# Sheet1.net
KiCad netlist of a schematic drawn in Altium Designer
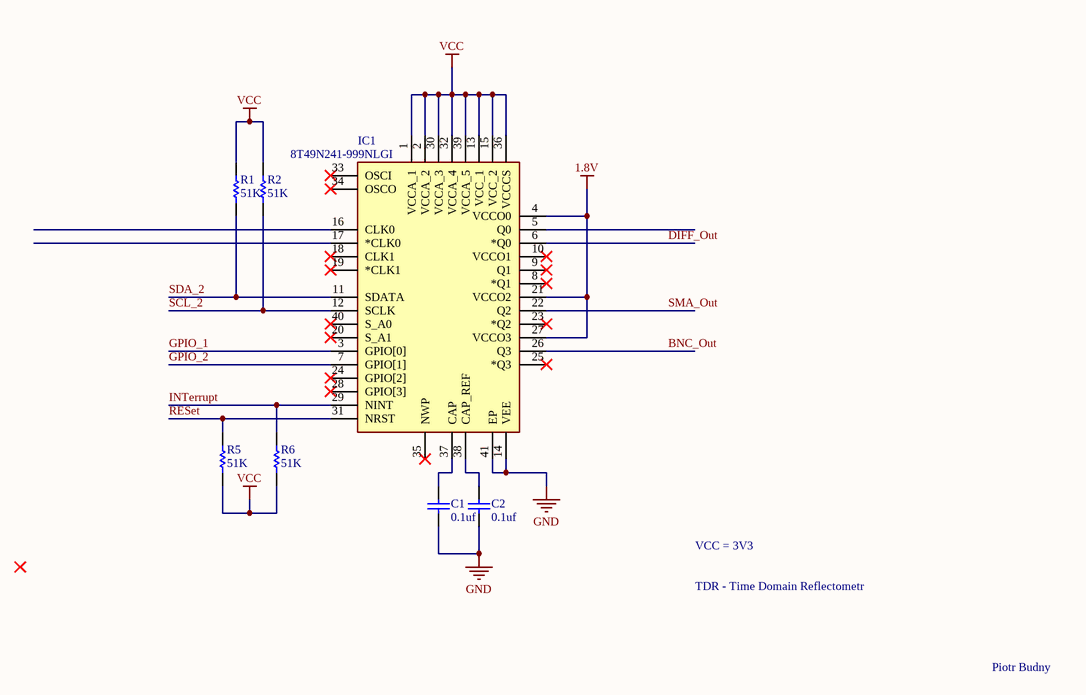
[diagram p0: Sheet1.SchDoc]

(export (version "E")
  (design (tool "Eeschema 10.0.6"))
  (components
    (comp (ref "C1")
      (value "0.1uf")
      (description "Capacitor")
      (libsource (lib "Simulation Generic Components") (part "Capacitor"))
    )
    (comp (ref "C2")
      (value "0.1uf")
      (description "Capacitor")
      (libsource (lib "Simulation Generic Components") (part "Capacitor"))
    )
    (comp (ref "IC1")
      (value "8T49N241-999NLGI")
      (footprint "SamacSys:QFN50P600X600X100-41N")
      (description "Integrated Circuit")
      (fields (field (name "MOUSER PART NUMBER") "972-8T49N241-999NLGI"))
      (libsource (lib "*") (part "8T49N241-999NLGI"))
    )
    (comp (ref "R1")
      (value "51K")
      (description "Resistor")
      (libsource (lib "Simulation Generic Components") (part "Resistor"))
    )
    (comp (ref "R2")
      (value "51K")
      (description "Resistor")
      (libsource (lib "Simulation Generic Components") (part "Resistor"))
    )
    (comp (ref "R5")
      (value "51K")
      (description "Resistor")
      (libsource (lib "Simulation Generic Components") (part "Resistor"))
    )
    (comp (ref "R6")
      (value "51K")
      (description "Resistor")
      (libsource (lib "Simulation Generic Components") (part "Resistor"))
    )
  )
  (nets
    (net (code "1") (name "/BNC_Out") (class "Default")
      (node (ref "IC1") (pin "26") (pinfunction "Q3_26") (pintype "passive"))
    )
    (net (code "2") (name "/DIFF_Out") (class "Default")
      (node (ref "IC1") (pin "6") (pinfunction "*Q0_6") (pintype "passive"))
    )
    (net (code "3") (name "/GPIO_1") (class "Default")
      (node (ref "IC1") (pin "3") (pinfunction "GPIO[0]_3") (pintype "passive"))
    )
    (net (code "4") (name "/GPIO_2") (class "Default")
      (node (ref "IC1") (pin "7") (pinfunction "GPIO[1]_7") (pintype "passive"))
    )
    (net (code "5") (name "/INTerrupt") (class "Default")
      (node (ref "IC1") (pin "29") (pinfunction "NINT_29") (pintype "passive"))
      (node (ref "R6") (pin "2") (pinfunction "2_2") (pintype "passive"))
    )
    (net (code "6") (name "/RESet") (class "Default")
      (node (ref "IC1") (pin "31") (pinfunction "NRST_31") (pintype "passive"))
      (node (ref "R5") (pin "2") (pinfunction "2_2") (pintype "passive"))
    )
    (net (code "7") (name "/SCL_2") (class "Default")
      (node (ref "IC1") (pin "12") (pinfunction "SCLK_12") (pintype "passive"))
      (node (ref "R2") (pin "1") (pinfunction "1_1") (pintype "passive"))
    )
    (net (code "8") (name "/SDA_2") (class "Default")
      (node (ref "IC1") (pin "11") (pinfunction "SDATA_11") (pintype "passive"))
      (node (ref "R1") (pin "1") (pinfunction "1_1") (pintype "passive"))
    )
    (net (code "9") (name "/SMA_Out") (class "Default")
      (node (ref "IC1") (pin "22") (pinfunction "Q2_22") (pintype "passive"))
    )
    (net (code "10") (name "1.8V") (class "Default")
      (node (ref "IC1") (pin "21") (pinfunction "VCCO2_21") (pintype "passive"))
      (node (ref "IC1") (pin "27") (pinfunction "VCCO3_27") (pintype "passive"))
      (node (ref "IC1") (pin "4") (pinfunction "VCCO0_4") (pintype "passive"))
    )
    (net (code "11") (name "GND") (class "Default")
      (node (ref "C1") (pin "2") (pinfunction "2_2") (pintype "passive"))
      (node (ref "C2") (pin "1") (pinfunction "1_1") (pintype "passive"))
      (node (ref "IC1") (pin "14") (pinfunction "VEE_14") (pintype "passive"))
      (node (ref "IC1") (pin "41") (pinfunction "EP_41") (pintype "passive"))
    )
    (net (code "12") (name "Net-(IC1-CAP)") (class "Default")
      (node (ref "C1") (pin "1") (pinfunction "1_1") (pintype "passive"))
      (node (ref "IC1") (pin "37") (pinfunction "CAP_37") (pintype "passive"))
    )
    (net (code "13") (name "Net-(IC1-CAP_REF)") (class "Default")
      (node (ref "C2") (pin "2") (pinfunction "2_2") (pintype "passive"))
      (node (ref "IC1") (pin "38") (pinfunction "CAP_REF_38") (pintype "passive"))
    )
    (net (code "14") (name "VCC") (class "Default")
      (node (ref "IC1") (pin "1") (pinfunction "VCCA_1_1") (pintype "passive"))
      (node (ref "IC1") (pin "13") (pinfunction "VCC_1_13") (pintype "passive"))
      (node (ref "IC1") (pin "15") (pinfunction "VCC_2_15") (pintype "passive"))
      (node (ref "IC1") (pin "2") (pinfunction "VCCA_2_2") (pintype "passive"))
      (node (ref "IC1") (pin "30") (pinfunction "VCCA_3_30") (pintype "passive"))
      (node (ref "IC1") (pin "32") (pinfunction "VCCA_4_32") (pintype "passive"))
      (node (ref "IC1") (pin "36") (pinfunction "VCCCS_36") (pintype "passive"))
      (node (ref "IC1") (pin "39") (pinfunction "VCCA_5_39") (pintype "passive"))
      (node (ref "R1") (pin "2") (pinfunction "2_2") (pintype "passive"))
      (node (ref "R2") (pin "2") (pinfunction "2_2") (pintype "passive"))
      (node (ref "R5") (pin "1") (pinfunction "1_1") (pintype "passive"))
      (node (ref "R6") (pin "1") (pinfunction "1_1") (pintype "passive"))
    )
    (net (code "15") (name "unconnected-(IC1-*CLK0-Pad17)") (class "Default")
      (node (ref "IC1") (pin "17") (pinfunction "*CLK0_17") (pintype "passive"))
    )
    (net (code "16") (name "unconnected-(IC1-*CLK1-Pad19)") (class "Default")
      (node (ref "IC1") (pin "19") (pinfunction "*CLK1_19") (pintype "passive+no_connect"))
    )
    (net (code "17") (name "unconnected-(IC1-*Q1-Pad8)") (class "Default")
      (node (ref "IC1") (pin "8") (pinfunction "*Q1_8") (pintype "passive+no_connect"))
    )
    (net (code "18") (name "unconnected-(IC1-*Q2-Pad23)") (class "Default")
      (node (ref "IC1") (pin "23") (pinfunction "*Q2_23") (pintype "passive+no_connect"))
    )
    (net (code "19") (name "unconnected-(IC1-*Q3-Pad25)") (class "Default")
      (node (ref "IC1") (pin "25") (pinfunction "*Q3_25") (pintype "passive+no_connect"))
    )
    (net (code "20") (name "unconnected-(IC1-CLK0-Pad16)") (class "Default")
      (node (ref "IC1") (pin "16") (pinfunction "CLK0_16") (pintype "passive"))
    )
    (net (code "21") (name "unconnected-(IC1-CLK1-Pad18)") (class "Default")
      (node (ref "IC1") (pin "18") (pinfunction "CLK1_18") (pintype "passive+no_connect"))
    )
    (net (code "22") (name "unconnected-(IC1-GPIO[2]-Pad24)") (class "Default")
      (node (ref "IC1") (pin "24") (pinfunction "GPIO[2]_24") (pintype "passive+no_connect"))
    )
    (net (code "23") (name "unconnected-(IC1-GPIO[3]-Pad28)") (class "Default")
      (node (ref "IC1") (pin "28") (pinfunction "GPIO[3]_28") (pintype "passive+no_connect"))
    )
    (net (code "24") (name "unconnected-(IC1-NWP-Pad35)") (class "Default")
      (node (ref "IC1") (pin "35") (pinfunction "NWP_35") (pintype "passive+no_connect"))
    )
    (net (code "25") (name "unconnected-(IC1-OSCI-Pad33)") (class "Default")
      (node (ref "IC1") (pin "33") (pinfunction "OSCI_33") (pintype "passive+no_connect"))
    )
    (net (code "26") (name "unconnected-(IC1-OSCO-Pad34)") (class "Default")
      (node (ref "IC1") (pin "34") (pinfunction "OSCO_34") (pintype "passive+no_connect"))
    )
    (net (code "27") (name "unconnected-(IC1-Q0-Pad5)") (class "Default")
      (node (ref "IC1") (pin "5") (pinfunction "Q0_5") (pintype "passive"))
    )
    (net (code "28") (name "unconnected-(IC1-Q1-Pad9)") (class "Default")
      (node (ref "IC1") (pin "9") (pinfunction "Q1_9") (pintype "passive+no_connect"))
    )
    (net (code "29") (name "unconnected-(IC1-S_A0-Pad40)") (class "Default")
      (node (ref "IC1") (pin "40") (pinfunction "S_A0_40") (pintype "passive+no_connect"))
    )
    (net (code "30") (name "unconnected-(IC1-S_A1-Pad20)") (class "Default")
      (node (ref "IC1") (pin "20") (pinfunction "S_A1_20") (pintype "passive+no_connect"))
    )
    (net (code "31") (name "unconnected-(IC1-VCCO1-Pad10)") (class "Default")
      (node (ref "IC1") (pin "10") (pinfunction "VCCO1_10") (pintype "passive+no_connect"))
    )
  )
)
